# schematic.net
KiCad netlist of a schematic drawn in Altium Designer
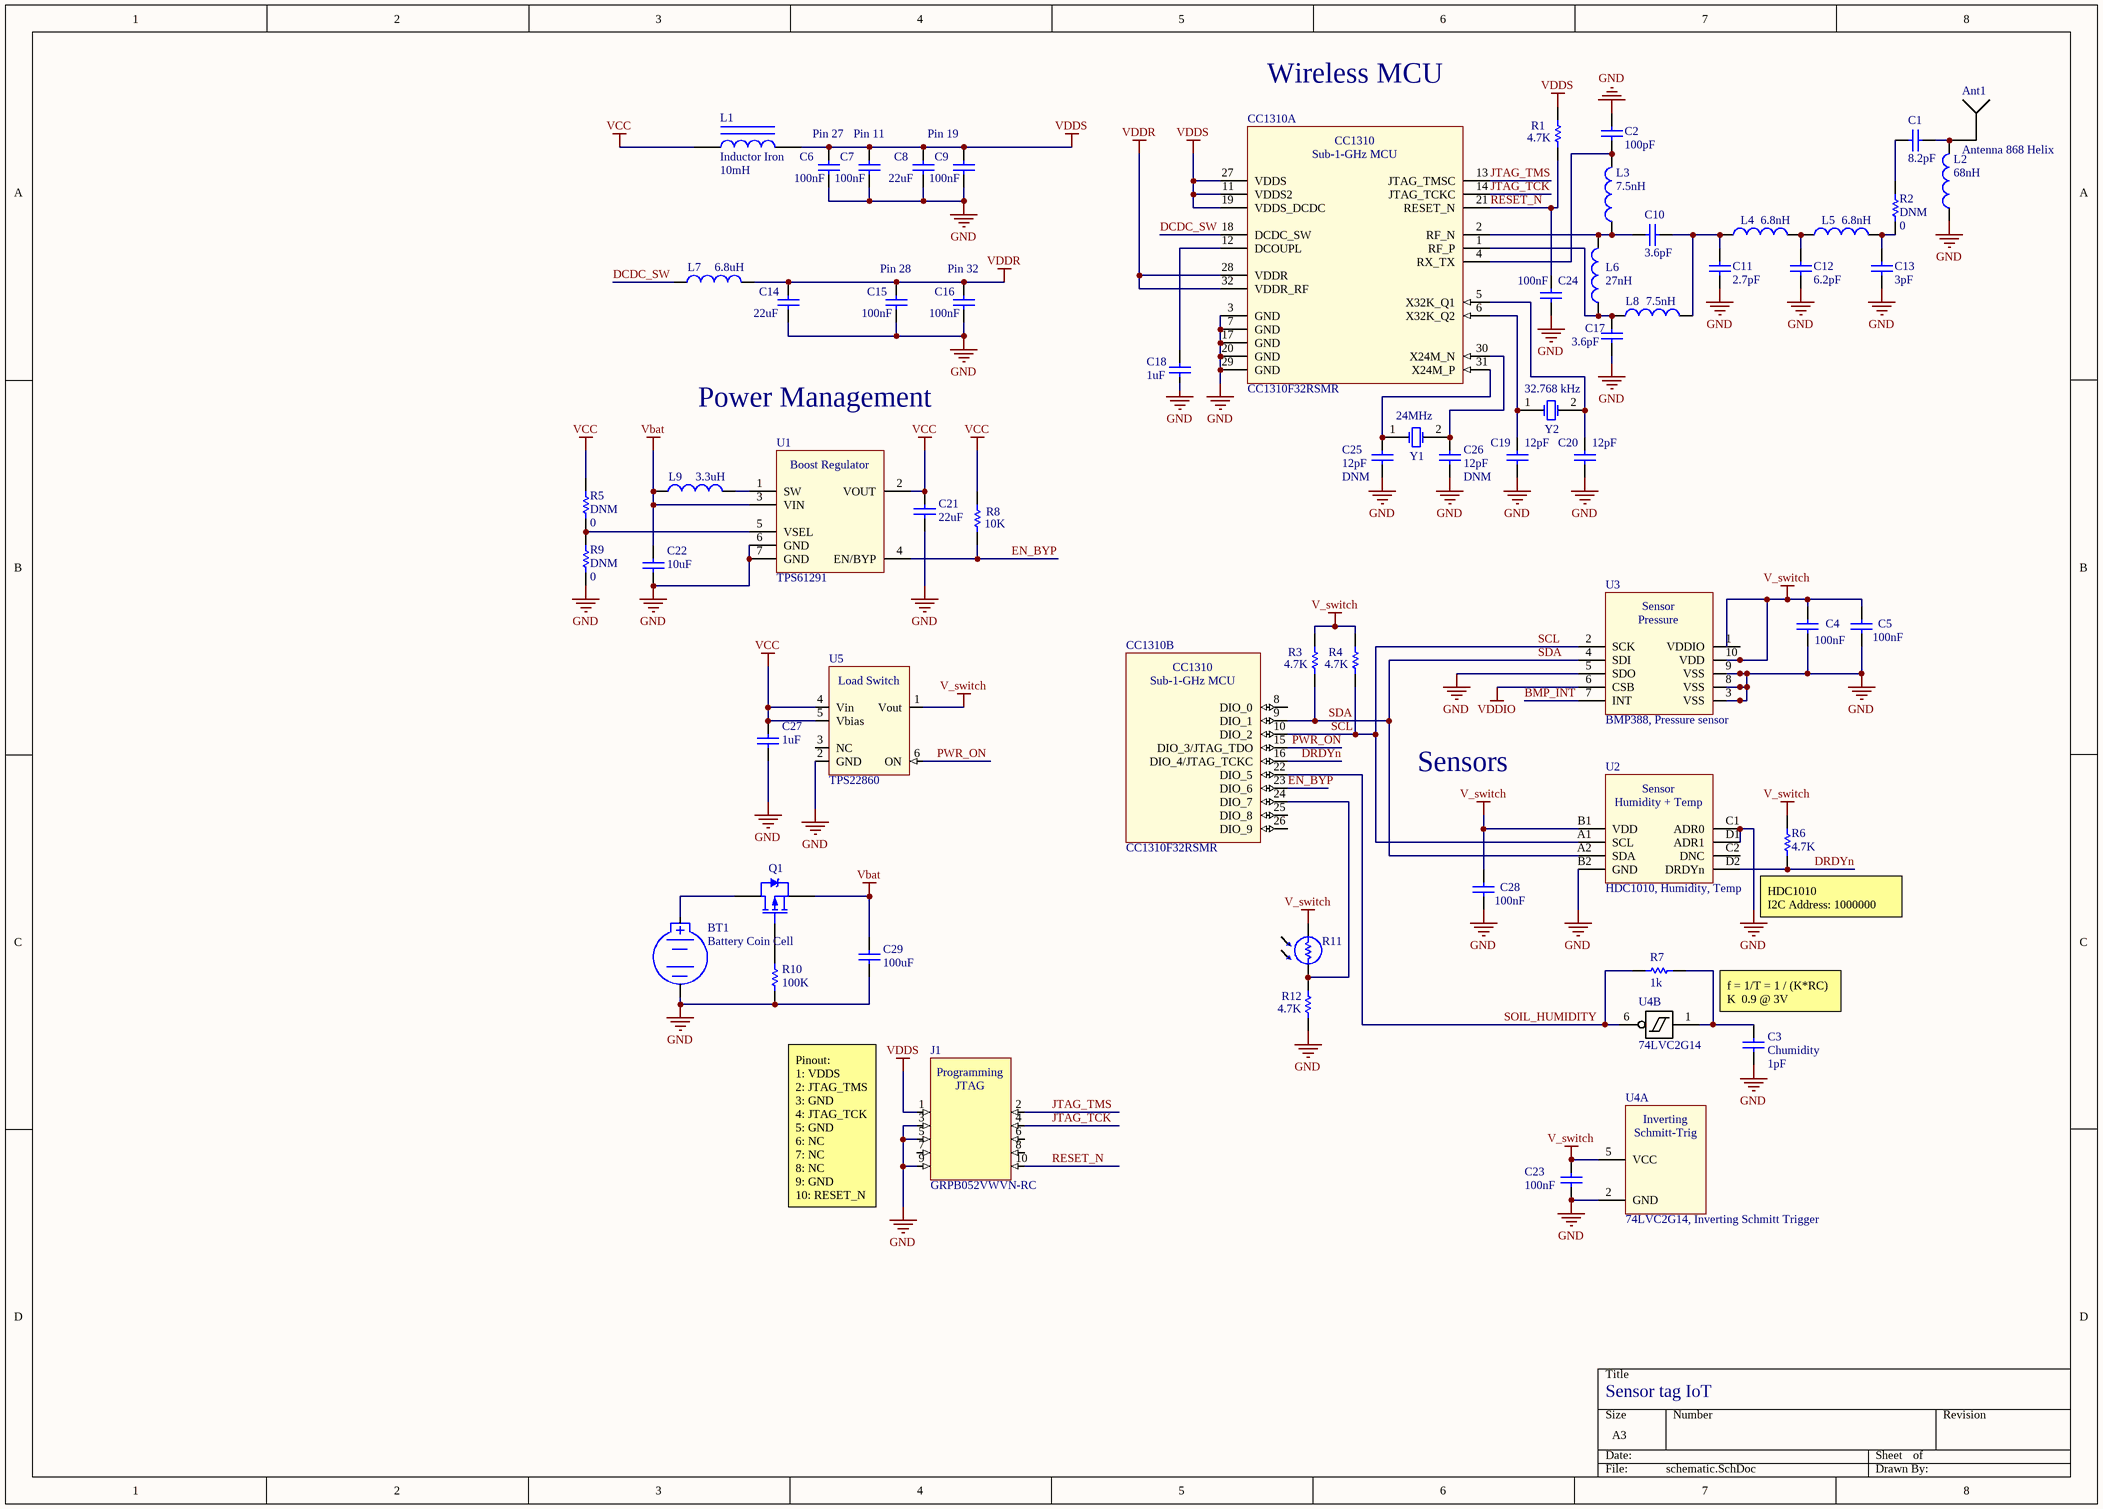
[diagram p0: schematic.SchDoc]

(export (version "E")
  (design (tool "Eeschema 10.0.6"))
  (components
    (comp (ref "Ant1")
      (value "Antenna 868 Helix")
      (footprint "Antenna_868_Helix")
      (libsource (lib "components") (part "Antenna 868 Helix"))
    )
    (comp (ref "BT1")
      (value "Battery Coin Cell")
      (footprint "SMTU2032-LF")
      (libsource (lib "components") (part "Battery Coin Cell"))
    )
    (comp (ref "C1")
      (value "8.2pF")
      (footprint "0402 (CAP)")
      (description "Capacitor")
      (fields (field (name "Comment") "Cap") (field (name "PUBLISHER") "Altium Limited"))
      (libsource (lib "Miscellaneous Devices") (part "Cap"))
    )
    (comp (ref "C2")
      (value "100pF")
      (footprint "0402 (CAP)")
      (description "Capacitor")
      (fields (field (name "Comment") "Cap") (field (name "PUBLISHER") "Altium Limited"))
      (libsource (lib "Miscellaneous Devices") (part "Cap"))
    )
    (comp (ref "C3")
      (value "Chumidity")
      (footprint "0402 (CAP)")
      (description "Capacitor")
      (fields (field (name "ALTIUM_VALUE") "1pF") (field (name "PUBLISHER") "Altium Limited"))
      (libsource (lib "Miscellaneous Devices") (part "Cap"))
    )
    (comp (ref "C4")
      (value "100nF")
      (footprint "0402 (CAP)")
      (description "Capacitor")
      (fields (field (name "Comment") "Cap") (field (name "PUBLISHER") "Altium Limited"))
      (libsource (lib "Miscellaneous Devices") (part "Cap"))
    )
    (comp (ref "C5")
      (value "100nF")
      (footprint "0402 (CAP)")
      (description "Capacitor")
      (fields (field (name "Comment") "Cap") (field (name "PUBLISHER") "Altium Limited"))
      (libsource (lib "Miscellaneous Devices") (part "Cap"))
    )
    (comp (ref "C6")
      (value "100nF")
      (footprint "0402 (CAP)")
      (description "Capacitor")
      (fields (field (name "Comment") "Cap") (field (name "PUBLISHER") "Altium Limited"))
      (libsource (lib "Miscellaneous Devices") (part "Cap"))
    )
    (comp (ref "C7")
      (value "100nF")
      (footprint "0402 (CAP)")
      (description "Capacitor")
      (fields (field (name "Comment") "Cap") (field (name "PUBLISHER") "Altium Limited"))
      (libsource (lib "Miscellaneous Devices") (part "Cap"))
    )
    (comp (ref "C8")
      (value "22uF")
      (footprint "0402 (CAP)")
      (description "Capacitor")
      (fields (field (name "Comment") "Cap") (field (name "PUBLISHER") "Altium Limited"))
      (libsource (lib "Miscellaneous Devices") (part "Cap"))
    )
    (comp (ref "C9")
      (value "100nF")
      (footprint "0402 (CAP)")
      (description "Capacitor")
      (fields (field (name "Comment") "Cap") (field (name "PUBLISHER") "Altium Limited"))
      (libsource (lib "Miscellaneous Devices") (part "Cap"))
    )
    (comp (ref "C10")
      (value "3.6pF")
      (footprint "0402 (CAP)")
      (description "Capacitor")
      (fields (field (name "Comment") "Cap") (field (name "PUBLISHER") "Altium Limited"))
      (libsource (lib "Miscellaneous Devices") (part "Cap"))
    )
    (comp (ref "C11")
      (value "2.7pF")
      (footprint "0402 (CAP)")
      (description "Capacitor")
      (fields (field (name "Comment") "Cap") (field (name "PUBLISHER") "Altium Limited"))
      (libsource (lib "Miscellaneous Devices") (part "Cap"))
    )
    (comp (ref "C12")
      (value "6.2pF")
      (footprint "0402 (CAP)")
      (description "Capacitor")
      (fields (field (name "Comment") "Cap") (field (name "PUBLISHER") "Altium Limited"))
      (libsource (lib "Miscellaneous Devices") (part "Cap"))
    )
    (comp (ref "C13")
      (value "3pF")
      (footprint "0402 (CAP)")
      (description "Capacitor")
      (fields (field (name "Comment") "Cap") (field (name "PUBLISHER") "Altium Limited"))
      (libsource (lib "Miscellaneous Devices") (part "Cap"))
    )
    (comp (ref "C14")
      (value "22uF")
      (footprint "0402 (CAP)")
      (description "Capacitor")
      (fields (field (name "Comment") "Cap") (field (name "PUBLISHER") "Altium Limited"))
      (libsource (lib "Miscellaneous Devices") (part "Cap"))
    )
    (comp (ref "C15")
      (value "100nF")
      (footprint "0402 (CAP)")
      (description "Capacitor")
      (fields (field (name "Comment") "Cap") (field (name "PUBLISHER") "Altium Limited"))
      (libsource (lib "Miscellaneous Devices") (part "Cap"))
    )
    (comp (ref "C16")
      (value "100nF")
      (footprint "0402 (CAP)")
      (description "Capacitor")
      (fields (field (name "Comment") "Cap") (field (name "PUBLISHER") "Altium Limited"))
      (libsource (lib "Miscellaneous Devices") (part "Cap"))
    )
    (comp (ref "C17")
      (value "3.6pF")
      (footprint "0402 (CAP)")
      (description "Capacitor")
      (fields (field (name "Comment") "Cap") (field (name "PUBLISHER") "Altium Limited"))
      (libsource (lib "Miscellaneous Devices") (part "Cap"))
    )
    (comp (ref "C18")
      (value "1uF")
      (footprint "0402 (CAP)")
      (description "Capacitor")
      (fields (field (name "Comment") "Cap") (field (name "PUBLISHER") "Altium Limited"))
      (libsource (lib "Miscellaneous Devices") (part "Cap"))
    )
    (comp (ref "C19")
      (value "12pF")
      (footprint "0402 (CAP)")
      (description "Capacitor")
      (fields (field (name "Comment") "Cap") (field (name "PUBLISHER") "Altium Limited"))
      (libsource (lib "Miscellaneous Devices") (part "Cap"))
    )
    (comp (ref "C20")
      (value "12pF")
      (footprint "0402 (CAP)")
      (description "Capacitor")
      (fields (field (name "Comment") "Cap") (field (name "PUBLISHER") "Altium Limited"))
      (libsource (lib "Miscellaneous Devices") (part "Cap"))
    )
    (comp (ref "C21")
      (value "22uF")
      (footprint "0402 (CAP)")
      (description "Capacitor")
      (fields (field (name "Comment") "Cap") (field (name "PUBLISHER") "Altium Limited"))
      (libsource (lib "Miscellaneous Devices") (part "Cap"))
    )
    (comp (ref "C22")
      (value "10uF")
      (footprint "0402 (CAP)")
      (description "Capacitor")
      (fields (field (name "Comment") "Cap") (field (name "PUBLISHER") "Altium Limited"))
      (libsource (lib "Miscellaneous Devices") (part "Cap"))
    )
    (comp (ref "C23")
      (value "100nF")
      (footprint "0402 (CAP)")
      (description "Capacitor")
      (fields (field (name "Comment") "Cap") (field (name "PUBLISHER") "Altium Limited"))
      (libsource (lib "Miscellaneous Devices") (part "Cap"))
    )
    (comp (ref "C24")
      (value "100nF")
      (footprint "0402 (CAP)")
      (description "Capacitor")
      (fields (field (name "Comment") "Cap") (field (name "PUBLISHER") "Altium Limited"))
      (libsource (lib "Miscellaneous Devices") (part "Cap"))
    )
    (comp (ref "C25")
      (value "DNM")
      (footprint "0402 (CAP)")
      (description "Capacitor")
      (fields (field (name "ALTIUM_VALUE") "12pF") (field (name "PUBLISHER") "Altium Limited"))
      (libsource (lib "Miscellaneous Devices") (part "Cap"))
    )
    (comp (ref "C26")
      (value "DNM")
      (footprint "0402 (CAP)")
      (description "Capacitor")
      (fields (field (name "ALTIUM_VALUE") "12pF") (field (name "PUBLISHER") "Altium Limited"))
      (libsource (lib "Miscellaneous Devices") (part "Cap"))
    )
    (comp (ref "C27")
      (value "1uF")
      (footprint "0402 (CAP)")
      (description "Capacitor")
      (fields (field (name "Comment") "Cap") (field (name "PUBLISHER") "Altium Limited"))
      (libsource (lib "Miscellaneous Devices") (part "Cap"))
    )
    (comp (ref "C28")
      (value "100nF")
      (footprint "0402 (CAP)")
      (description "Capacitor")
      (fields (field (name "Comment") "Cap") (field (name "PUBLISHER") "Altium Limited"))
      (libsource (lib "Miscellaneous Devices") (part "Cap"))
    )
    (comp (ref "C29")
      (value "100uF")
      (footprint "0402 (CAP)")
      (description "Capacitor")
      (fields (field (name "Comment") "Cap") (field (name "PUBLISHER") "Altium Limited"))
      (libsource (lib "Miscellaneous Devices") (part "Cap"))
    )
    (comp (ref "CC1310")
      (value "CC1310F32RSMR")
      (footprint "CC1310F32RSMR")
      (libsource (lib "components") (part "CC1310F32RSMR"))
    )
    (comp (ref "J1") (value "GRPB052VWVN-RC") (libsource (lib "connectors") (part "GRPB052VWVN-RC")))
    (comp (ref "L1")
      (value "Inductor Iron")
      (footprint "0603 (IND)")
      (description "Magnetic-Core Inductor")
      (fields (field (name "ALTIUM_VALUE") "10mH") (field (name "PUBLISHER") "Altium Limited"))
      (libsource (lib "Miscellaneous Devices") (part "Inductor Iron"))
    )
    (comp (ref "L2")
      (value "68nH")
      (footprint "0603 (IND)")
      (description "Inductor")
      (fields (field (name "PUBLISHER") "Altium Limited"))
      (libsource (lib "Miscellaneous Devices") (part "Inductor"))
    )
    (comp (ref "L3")
      (value "7.5nH")
      (footprint "0603 (IND)")
      (description "Inductor")
      (fields (field (name "PUBLISHER") "Altium Limited"))
      (libsource (lib "") (part "Inductor_1"))
    )
    (comp (ref "L4")
      (value "6.8nH")
      (footprint "0603 (IND)")
      (description "Inductor")
      (fields (field (name "PUBLISHER") "Altium Limited"))
      (libsource (lib "Miscellaneous Devices") (part "Inductor"))
    )
    (comp (ref "L5")
      (value "6.8nH")
      (footprint "0603 (IND)")
      (description "Inductor")
      (fields (field (name "PUBLISHER") "Altium Limited"))
      (libsource (lib "Miscellaneous Devices") (part "Inductor"))
    )
    (comp (ref "L6")
      (value "27nH")
      (footprint "0603 (IND)")
      (description "Inductor")
      (fields (field (name "PUBLISHER") "Altium Limited"))
      (libsource (lib "Miscellaneous Devices") (part "Inductor"))
    )
    (comp (ref "L7")
      (value "6.8uH")
      (footprint "0603 (IND)")
      (description "Inductor")
      (fields (field (name "PUBLISHER") "Altium Limited"))
      (libsource (lib "") (part "Inductor_1"))
    )
    (comp (ref "L8")
      (value "7.5nH")
      (footprint "0603 (IND)")
      (description "Inductor")
      (fields (field (name "PUBLISHER") "Altium Limited"))
      (libsource (lib "Miscellaneous Devices") (part "Inductor"))
    )
    (comp (ref "L9")
      (value "3.3uH")
      (footprint "0603 (IND)")
      (description "Inductor")
      (fields (field (name "PUBLISHER") "Altium Limited"))
      (libsource (lib "") (part "Inductor_1"))
    )
    (comp (ref "Q1")
      (value "PMOS-2")
      (footprint "TO-220AB")
      (description "P-Channel Power MOSFET")
      (fields (field (name "PUBLISHER") "Altium Limited"))
      (libsource (lib "Miscellaneous Devices") (part "PMOS-2"))
    )
    (comp (ref "R1")
      (value "4.7K")
      (footprint "0402 (RES)")
      (description "Resistor")
      (fields (field (name "Comment") "Res1") (field (name "PUBLISHER") "Altium Limited"))
      (libsource (lib "Miscellaneous Devices") (part "Res1"))
    )
    (comp (ref "R2")
      (value "DNM")
      (footprint "0402 (RES)")
      (description "Resistor")
      (fields (field (name "ALTIUM_VALUE") "0") (field (name "PUBLISHER") "Altium Limited"))
      (libsource (lib "Miscellaneous Devices") (part "Res1"))
    )
    (comp (ref "R3")
      (value "4.7K")
      (footprint "0402 (RES)")
      (description "Resistor")
      (fields (field (name "Comment") "Res1") (field (name "PUBLISHER") "Altium Limited"))
      (libsource (lib "Miscellaneous Devices") (part "Res1"))
    )
    (comp (ref "R4")
      (value "4.7K")
      (footprint "0402 (RES)")
      (description "Resistor")
      (fields (field (name "Comment") "Res1") (field (name "PUBLISHER") "Altium Limited"))
      (libsource (lib "Miscellaneous Devices") (part "Res1"))
    )
    (comp (ref "R5")
      (value "DNM")
      (footprint "0402 (RES)")
      (description "Resistor")
      (fields (field (name "ALTIUM_VALUE") "0") (field (name "PUBLISHER") "Altium Limited"))
      (libsource (lib "Miscellaneous Devices") (part "Res1"))
    )
    (comp (ref "R6")
      (value "4.7K")
      (footprint "0402 (RES)")
      (description "Resistor")
      (fields (field (name "Comment") "Res1") (field (name "PUBLISHER") "Altium Limited"))
      (libsource (lib "Miscellaneous Devices") (part "Res1"))
    )
    (comp (ref "R7")
      (value "1k")
      (footprint "0402 (RES)")
      (description "Resistor")
      (fields (field (name "Comment") "Rcharge") (field (name "PUBLISHER") "Altium Limited"))
      (libsource (lib "Miscellaneous Devices") (part "Res1"))
    )
    (comp (ref "R8")
      (value "10K")
      (footprint "0402 (RES)")
      (description "Resistor")
      (fields (field (name "Comment") "Res1") (field (name "PUBLISHER") "Altium Limited"))
      (libsource (lib "Miscellaneous Devices") (part "Res1"))
    )
    (comp (ref "R9")
      (value "DNM")
      (footprint "0402 (RES)")
      (description "Resistor")
      (fields (field (name "ALTIUM_VALUE") "0") (field (name "PUBLISHER") "Altium Limited"))
      (libsource (lib "Miscellaneous Devices") (part "Res1"))
    )
    (comp (ref "R10")
      (value "100K")
      (footprint "0402 (RES)")
      (description "Resistor")
      (fields (field (name "Comment") "Res1") (field (name "PUBLISHER") "Altium Limited"))
      (libsource (lib "Miscellaneous Devices") (part "Res1"))
    )
    (comp (ref "R11") (value "Photo Resistor") (libsource (lib "components") (part "Photo Resistor")))
    (comp (ref "R12")
      (value "4.7K")
      (footprint "0402 (RES)")
      (description "Resistor")
      (fields (field (name "Comment") "Res1") (field (name "PUBLISHER") "Altium Limited"))
      (libsource (lib "Miscellaneous Devices") (part "Res1"))
    )
    (comp (ref "U1")
      (value "TPS61291")
      (footprint "TPS61291")
      (libsource (lib "components") (part "TPS61291"))
    )
    (comp (ref "U2")
      (value "HDC1010, Humidity, Temp")
      (footprint "HDC1010")
      (libsource (lib "components") (part "HDC1010"))
    )
    (comp (ref "U3")
      (value "BMP388, Pressure sensor")
      (footprint "BMP388")
      (libsource (lib "components") (part "BMP388"))
    )
    (comp (ref "U4")
      (value "74LVC2G14, Inverting Schmitt Trigger")
      (footprint "74LVC2G14")
      (libsource (lib "components") (part "74LVC2G14"))
    )
    (comp (ref "U5")
      (value "TPS22860")
      (footprint "SOT23-5")
      (libsource (lib "components") (part "TPS22860"))
    )
    (comp (ref "Y1")
      (value "24MHz")
      (footprint "R38")
      (description "Crystal Oscillator")
      (fields (field (name "PUBLISHER") "Altium Limited"))
      (libsource (lib "Miscellaneous Devices") (part "XTAL"))
    )
    (comp (ref "Y2")
      (value "32.768 kHz")
      (footprint "R38")
      (description "Crystal Oscillator")
      (fields (field (name "PUBLISHER") "Altium Limited"))
      (libsource (lib "Miscellaneous Devices") (part "XTAL"))
    )
  )
  (nets
    (net (code "1") (name "/BMP_INT") (class "Default")
      (node (ref "U3") (pin "7") (pinfunction "INT_7") (pintype "passive"))
    )
    (net (code "2") (name "/DCDC_SW") (class "Default")
      (node (ref "CC1310") (pin "18") (pinfunction "DCDC_SW_18") (pintype "power_in"))
      (node (ref "L7") (pin "1") (pinfunction "1_1") (pintype "passive"))
    )
    (net (code "3") (name "/DRDYn") (class "Default")
      (node (ref "CC1310") (pin "16") (pinfunction "DIO_4/JTAG_TCKC_16") (pintype "bidirectional"))
      (node (ref "R6") (pin "2") (pinfunction "2_2") (pintype "passive"))
      (node (ref "U2") (pin "D2") (pinfunction "DRDYn_D2") (pintype "passive"))
    )
    (net (code "4") (name "/EN_BYP") (class "Default")
      (node (ref "CC1310") (pin "23") (pinfunction "DIO_6_23") (pintype "bidirectional"))
      (node (ref "R8") (pin "2") (pinfunction "2_2") (pintype "passive"))
      (node (ref "U1") (pin "4") (pinfunction "EN/BYP_4") (pintype "passive"))
    )
    (net (code "5") (name "/JTAG_TCK") (class "Default")
      (node (ref "CC1310") (pin "14") (pinfunction "JTAG_TCKC_14") (pintype "passive"))
      (node (ref "J1") (pin "4") (pinfunction "JTAG_TCK_4") (pintype "input"))
    )
    (net (code "6") (name "/JTAG_TMS") (class "Default")
      (node (ref "CC1310") (pin "13") (pinfunction "JTAG_TMSC_13") (pintype "passive"))
      (node (ref "J1") (pin "2") (pinfunction "JTAG_TMS_2") (pintype "input"))
    )
    (net (code "7") (name "/PWR_ON") (class "Default")
      (node (ref "CC1310") (pin "15") (pinfunction "DIO_3/JTAG_TDO_15") (pintype "bidirectional"))
      (node (ref "U5") (pin "6") (pinfunction "ON_6") (pintype "input"))
    )
    (net (code "8") (name "/RESET_N") (class "Default")
      (node (ref "C24") (pin "1") (pinfunction "1_1") (pintype "passive"))
      (node (ref "CC1310") (pin "21") (pinfunction "RESET_N_21") (pintype "passive"))
      (node (ref "J1") (pin "10") (pinfunction "RESET_N_10") (pintype "input"))
      (node (ref "R1") (pin "1") (pinfunction "1_1") (pintype "passive"))
    )
    (net (code "9") (name "/SCL") (class "Default")
      (node (ref "CC1310") (pin "10") (pinfunction "DIO_2_10") (pintype "bidirectional"))
      (node (ref "R4") (pin "1") (pinfunction "1_1") (pintype "passive"))
      (node (ref "U2") (pin "A1") (pinfunction "SCL_A1") (pintype "passive"))
      (node (ref "U3") (pin "2") (pinfunction "SCK_2") (pintype "passive"))
    )
    (net (code "10") (name "/SDA") (class "Default")
      (node (ref "CC1310") (pin "9") (pinfunction "DIO_1_9") (pintype "bidirectional"))
      (node (ref "R3") (pin "1") (pinfunction "1_1") (pintype "passive"))
      (node (ref "U2") (pin "A2") (pinfunction "SDA_A2") (pintype "passive"))
      (node (ref "U3") (pin "4") (pinfunction "SDI_4") (pintype "passive"))
    )
    (net (code "11") (name "/SOIL_HUMIDITY") (class "Default")
      (node (ref "CC1310") (pin "22") (pinfunction "DIO_5_22") (pintype "bidirectional"))
      (node (ref "R7") (pin "2") (pinfunction "2_2") (pintype "passive"))
      (node (ref "U4") (pin "6") (pinfunction "1Y_6") (pintype "passive"))
    )
    (net (code "12") (name "GND") (class "Default")
      (node (ref "BT1") (pin "2") (pinfunction "Negative_2") (pintype "passive"))
      (node (ref "C11") (pin "2") (pinfunction "2_2") (pintype "passive"))
      (node (ref "C12") (pin "2") (pinfunction "2_2") (pintype "passive"))
      (node (ref "C13") (pin "2") (pinfunction "2_2") (pintype "passive"))
      (node (ref "C14") (pin "1") (pinfunction "1_1") (pintype "passive"))
      (node (ref "C15") (pin "1") (pinfunction "1_1") (pintype "passive"))
      (node (ref "C16") (pin "1") (pinfunction "1_1") (pintype "passive"))
      (node (ref "C17") (pin "2") (pinfunction "2_2") (pintype "passive"))
      (node (ref "C18") (pin "1") (pinfunction "1_1") (pintype "passive"))
      (node (ref "C19") (pin "1") (pinfunction "1_1") (pintype "passive"))
      (node (ref "C2") (pin "1") (pinfunction "1_1") (pintype "passive"))
      (node (ref "C20") (pin "1") (pinfunction "1_1") (pintype "passive"))
      (node (ref "C21") (pin "1") (pinfunction "1_1") (pintype "passive"))
      (node (ref "C22") (pin "1") (pinfunction "1_1") (pintype "passive"))
      (node (ref "C23") (pin "1") (pinfunction "1_1") (pintype "passive"))
      (node (ref "C24") (pin "2") (pinfunction "2_2") (pintype "passive"))
      (node (ref "C25") (pin "1") (pinfunction "1_1") (pintype "passive"))
      (node (ref "C26") (pin "1") (pinfunction "1_1") (pintype "passive"))
      (node (ref "C27") (pin "1") (pinfunction "1_1") (pintype "passive"))
      (node (ref "C28") (pin "1") (pinfunction "1_1") (pintype "passive"))
      (node (ref "C29") (pin "1") (pinfunction "1_1") (pintype "passive"))
      (node (ref "C3") (pin "1") (pinfunction "1_1") (pintype "passive"))
      (node (ref "C4") (pin "1") (pinfunction "1_1") (pintype "passive"))
      (node (ref "C5") (pin "1") (pinfunction "1_1") (pintype "passive"))
      (node (ref "C6") (pin "1") (pinfunction "1_1") (pintype "passive"))
      (node (ref "C7") (pin "1") (pinfunction "1_1") (pintype "passive"))
      (node (ref "C8") (pin "1") (pinfunction "1_1") (pintype "passive"))
      (node (ref "C9") (pin "1") (pinfunction "1_1") (pintype "passive"))
      (node (ref "CC1310") (pin "17") (pinfunction "GND_17") (pintype "passive"))
      (node (ref "CC1310") (pin "20") (pinfunction "GND_20") (pintype "passive"))
      (node (ref "CC1310") (pin "29") (pinfunction "GND_29") (pintype "passive"))
      (node (ref "CC1310") (pin "3") (pinfunction "GND_3") (pintype "passive"))
      (node (ref "CC1310") (pin "7") (pinfunction "GND_7") (pintype "passive"))
      (node (ref "J1") (pin "3") (pinfunction "GND_3") (pintype "input"))
      (node (ref "J1") (pin "5") (pinfunction "GND_5") (pintype "input"))
      (node (ref "J1") (pin "9") (pinfunction "GND_9") (pintype "input"))
      (node (ref "L2") (pin "2") (pinfunction "2_2") (pintype "passive"))
      (node (ref "R10") (pin "2") (pinfunction "2_2") (pintype "passive"))
      (node (ref "R12") (pin "1") (pinfunction "1_1") (pintype "passive"))
      (node (ref "R9") (pin "2") (pinfunction "2_2") (pintype "passive"))
      (node (ref "U1") (pin "6") (pinfunction "GND_6") (pintype "passive"))
      (node (ref "U1") (pin "7") (pinfunction "GND_7") (pintype "passive"))
      (node (ref "U2") (pin "B2") (pinfunction "GND_B2") (pintype "passive"))
      (node (ref "U2") (pin "C1") (pinfunction "ADR0_C1") (pintype "passive"))
      (node (ref "U2") (pin "D1") (pinfunction "ADR1_D1") (pintype "passive"))
      (node (ref "U3") (pin "3") (pinfunction "VSS_3") (pintype "passive"))
      (node (ref "U3") (pin "5") (pinfunction "SDO_5") (pintype "passive"))
      (node (ref "U3") (pin "8") (pinfunction "VSS_8") (pintype "passive"))
      (node (ref "U3") (pin "9") (pinfunction "VSS_9") (pintype "passive"))
      (node (ref "U4") (pin "2") (pinfunction "GND_2") (pintype "passive"))
      (node (ref "U5") (pin "2") (pinfunction "GND_2") (pintype "power_in"))
    )
    (net (code "13") (name "Net-(Ant1-Pad0)") (class "Default")
      (node (ref "Ant1") (pin "0") (pinfunction "0_0") (pintype "passive"))
      (node (ref "C1") (pin "2") (pinfunction "2_2") (pintype "passive"))
      (node (ref "L2") (pin "1") (pinfunction "1_1") (pintype "passive"))
    )
    (net (code "14") (name "Net-(BT1-Positive)") (class "Default")
      (node (ref "BT1") (pin "1") (pinfunction "Positive_1") (pintype "passive"))
      (node (ref "Q1") (pin "2") (pinfunction "D_2") (pintype "passive"))
    )
    (net (code "15") (name "Net-(C1-Pad1)") (class "Default")
      (node (ref "C1") (pin "1") (pinfunction "1_1") (pintype "passive"))
      (node (ref "R2") (pin "1") (pinfunction "1_1") (pintype "passive"))
    )
    (net (code "16") (name "Net-(C10-Pad2)") (class "Default")
      (node (ref "C10") (pin "2") (pinfunction "2_2") (pintype "passive"))
      (node (ref "C11") (pin "1") (pinfunction "1_1") (pintype "passive"))
      (node (ref "L4") (pin "2") (pinfunction "2_2") (pintype "passive"))
      (node (ref "L8") (pin "1") (pinfunction "1_1") (pintype "passive"))
    )
    (net (code "17") (name "Net-(C12-Pad1)") (class "Default")
      (node (ref "C12") (pin "1") (pinfunction "1_1") (pintype "passive"))
      (node (ref "L4") (pin "1") (pinfunction "1_1") (pintype "passive"))
      (node (ref "L5") (pin "2") (pinfunction "2_2") (pintype "passive"))
    )
    (net (code "18") (name "Net-(C13-Pad1)") (class "Default")
      (node (ref "C13") (pin "1") (pinfunction "1_1") (pintype "passive"))
      (node (ref "L5") (pin "1") (pinfunction "1_1") (pintype "passive"))
      (node (ref "R2") (pin "2") (pinfunction "2_2") (pintype "passive"))
    )
    (net (code "19") (name "Net-(CC1310A-DCOUPL)") (class "Default")
      (node (ref "C18") (pin "2") (pinfunction "2_2") (pintype "passive"))
      (node (ref "CC1310") (pin "12") (pinfunction "DCOUPL_12") (pintype "power_in"))
    )
    (net (code "20") (name "Net-(CC1310A-RF_N)") (class "Default")
      (node (ref "C10") (pin "1") (pinfunction "1_1") (pintype "passive"))
      (node (ref "CC1310") (pin "2") (pinfunction "RF_N_2") (pintype "passive"))
      (node (ref "L3") (pin "1") (pinfunction "1_1") (pintype "passive"))
      (node (ref "L6") (pin "1") (pinfunction "1_1") (pintype "passive"))
    )
    (net (code "21") (name "Net-(CC1310A-RF_P)") (class "Default")
      (node (ref "C17") (pin "1") (pinfunction "1_1") (pintype "passive"))
      (node (ref "CC1310") (pin "1") (pinfunction "RF_P_1") (pintype "passive"))
      (node (ref "L6") (pin "2") (pinfunction "2_2") (pintype "passive"))
      (node (ref "L8") (pin "2") (pinfunction "2_2") (pintype "passive"))
    )
    (net (code "22") (name "Net-(CC1310A-RX_TX)") (class "Default")
      (node (ref "C2") (pin "2") (pinfunction "2_2") (pintype "passive"))
      (node (ref "CC1310") (pin "4") (pinfunction "RX_TX_4") (pintype "passive"))
      (node (ref "L3") (pin "2") (pinfunction "2_2") (pintype "passive"))
    )
    (net (code "23") (name "Net-(CC1310A-X24M_N)") (class "Default")
      (node (ref "C26") (pin "2") (pinfunction "2_2") (pintype "passive"))
      (node (ref "CC1310") (pin "30") (pinfunction "X24M_N_30") (pintype "input"))
      (node (ref "Y1") (pin "2") (pinfunction "OSC2_2") (pintype "passive"))
    )
    (net (code "24") (name "Net-(CC1310A-X24M_P)") (class "Default")
      (node (ref "C25") (pin "2") (pinfunction "2_2") (pintype "passive"))
      (node (ref "CC1310") (pin "31") (pinfunction "X24M_P_31") (pintype "input"))
      (node (ref "Y1") (pin "1") (pinfunction "OSC1_1") (pintype "passive"))
    )
    (net (code "25") (name "Net-(CC1310A-X32K_Q1)") (class "Default")
      (node (ref "C20") (pin "2") (pinfunction "2_2") (pintype "passive"))
      (node (ref "CC1310") (pin "5") (pinfunction "X32K_Q1_5") (pintype "input"))
      (node (ref "Y2") (pin "2") (pinfunction "OSC2_2") (pintype "passive"))
    )
    (net (code "26") (name "Net-(CC1310A-X32K_Q2)") (class "Default")
      (node (ref "C19") (pin "2") (pinfunction "2_2") (pintype "passive"))
      (node (ref "CC1310") (pin "6") (pinfunction "X32K_Q2_6") (pintype "input"))
      (node (ref "Y2") (pin "1") (pinfunction "OSC1_1") (pintype "passive"))
    )
    (net (code "27") (name "Net-(CC1310B-DIO_7)") (class "Default")
      (node (ref "CC1310") (pin "24") (pinfunction "DIO_7_24") (pintype "bidirectional"))
      (node (ref "R11") (pin "2") (pinfunction "2_2") (pintype "passive"))
      (node (ref "R12") (pin "2") (pinfunction "2_2") (pintype "passive"))
    )
    (net (code "28") (name "Net-(Q1-G)") (class "Default")
      (node (ref "Q1") (pin "1") (pinfunction "G_1") (pintype "passive"))
      (node (ref "R10") (pin "1") (pinfunction "1_1") (pintype "passive"))
    )
    (net (code "29") (name "Net-(U1-SW)") (class "Default")
      (node (ref "L9") (pin "2") (pinfunction "2_2") (pintype "passive"))
      (node (ref "U1") (pin "1") (pinfunction "SW_1") (pintype "passive"))
    )
    (net (code "30") (name "Net-(U1-VSEL)") (class "Default")
      (node (ref "R5") (pin "2") (pinfunction "2_2") (pintype "passive"))
      (node (ref "R9") (pin "1") (pinfunction "1_1") (pintype "passive"))
      (node (ref "U1") (pin "5") (pinfunction "VSEL_5") (pintype "passive"))
    )
    (net (code "31") (name "Net-(U4B-1A)") (class "Default")
      (node (ref "C3") (pin "2") (pinfunction "2_2") (pintype "passive"))
      (node (ref "R7") (pin "1") (pinfunction "1_1") (pintype "passive"))
      (node (ref "U4") (pin "1") (pinfunction "1A_1") (pintype "passive"))
    )
    (net (code "32") (name "VCC") (class "Default")
      (node (ref "C21") (pin "2") (pinfunction "2_2") (pintype "passive"))
      (node (ref "C27") (pin "2") (pinfunction "2_2") (pintype "passive"))
      (node (ref "L1") (pin "1") (pinfunction "1_1") (pintype "passive"))
      (node (ref "R5") (pin "1") (pinfunction "1_1") (pintype "passive"))
      (node (ref "R8") (pin "1") (pinfunction "1_1") (pintype "passive"))
      (node (ref "U1") (pin "2") (pinfunction "VOUT_2") (pintype "passive"))
      (node (ref "U5") (pin "4") (pinfunction "Vin_4") (pintype "power_in"))
      (node (ref "U5") (pin "5") (pinfunction "Vbias_5") (pintype "power_in"))
    )
    (net (code "33") (name "VDDIO") (class "Default")
      (node (ref "U3") (pin "6") (pinfunction "CSB_6") (pintype "passive"))
    )
    (net (code "34") (name "VDDR") (class "Default")
      (node (ref "C14") (pin "2") (pinfunction "2_2") (pintype "passive"))
      (node (ref "C15") (pin "2") (pinfunction "2_2") (pintype "passive"))
      (node (ref "C16") (pin "2") (pinfunction "2_2") (pintype "passive"))
      (node (ref "CC1310") (pin "28") (pinfunction "VDDR_28") (pintype "power_in"))
      (node (ref "CC1310") (pin "32") (pinfunction "VDDR_RF_32") (pintype "power_in"))
      (node (ref "L7") (pin "2") (pinfunction "2_2") (pintype "passive"))
    )
    (net (code "35") (name "VDDS") (class "Default")
      (node (ref "C6") (pin "2") (pinfunction "2_2") (pintype "passive"))
      (node (ref "C7") (pin "2") (pinfunction "2_2") (pintype "passive"))
      (node (ref "C8") (pin "2") (pinfunction "2_2") (pintype "passive"))
      (node (ref "C9") (pin "2") (pinfunction "2_2") (pintype "passive"))
      (node (ref "CC1310") (pin "11") (pinfunction "VDDS2_11") (pintype "passive"))
      (node (ref "CC1310") (pin "19") (pinfunction "VDDS_DCDC_19") (pintype "passive"))
      (node (ref "CC1310") (pin "27") (pinfunction "VDDS_27") (pintype "passive"))
      (node (ref "J1") (pin "1") (pinfunction "VDDS_1") (pintype "input"))
      (node (ref "L1") (pin "2") (pinfunction "2_2") (pintype "passive"))
      (node (ref "R1") (pin "2") (pinfunction "2_2") (pintype "passive"))
    )
    (net (code "36") (name "V_switch") (class "Default")
      (node (ref "C23") (pin "2") (pinfunction "2_2") (pintype "passive"))
      (node (ref "C28") (pin "2") (pinfunction "2_2") (pintype "passive"))
      (node (ref "C4") (pin "2") (pinfunction "2_2") (pintype "passive"))
      (node (ref "C5") (pin "2") (pinfunction "2_2") (pintype "passive"))
      (node (ref "R11") (pin "1") (pinfunction "1_1") (pintype "passive"))
      (node (ref "R3") (pin "2") (pinfunction "2_2") (pintype "passive"))
      (node (ref "R4") (pin "2") (pinfunction "2_2") (pintype "passive"))
      (node (ref "R6") (pin "1") (pinfunction "1_1") (pintype "passive"))
      (node (ref "U2") (pin "B1") (pinfunction "VDD_B1") (pintype "passive"))
      (node (ref "U3") (pin "10") (pinfunction "VDD_10") (pintype "passive"))
      (node (ref "U4") (pin "5") (pinfunction "VCC_5") (pintype "passive"))
      (node (ref "U5") (pin "1") (pinfunction "Vout_1") (pintype "power_in"))
    )
    (net (code "37") (name "Vbat") (class "Default")
      (node (ref "C22") (pin "2") (pinfunction "2_2") (pintype "passive"))
      (node (ref "C29") (pin "2") (pinfunction "2_2") (pintype "passive"))
      (node (ref "L9") (pin "1") (pinfunction "1_1") (pintype "passive"))
      (node (ref "Q1") (pin "3") (pinfunction "S_3") (pintype "passive"))
      (node (ref "U1") (pin "3") (pinfunction "VIN_3") (pintype "passive"))
    )
    (net (code "38") (name "unconnected-(CC1310B-DIO_0-Pad8)") (class "Default")
      (node (ref "CC1310") (pin "8") (pinfunction "DIO_0_8") (pintype "bidirectional"))
    )
    (net (code "39") (name "unconnected-(CC1310B-DIO_8-Pad25)") (class "Default")
      (node (ref "CC1310") (pin "25") (pinfunction "DIO_8_25") (pintype "bidirectional"))
    )
    (net (code "40") (name "unconnected-(CC1310B-DIO_9-Pad26)") (class "Default")
      (node (ref "CC1310") (pin "26") (pinfunction "DIO_9_26") (pintype "bidirectional"))
    )
    (net (code "41") (name "unconnected-(J1-NC-Pad6)") (class "Default")
      (node (ref "J1") (pin "6") (pinfunction "NC_6") (pintype "input"))
    )
    (net (code "42") (name "unconnected-(J1-NC-Pad7)") (class "Default")
      (node (ref "J1") (pin "7") (pinfunction "NC_7") (pintype "input"))
    )
    (net (code "43") (name "unconnected-(J1-NC-Pad8)") (class "Default")
      (node (ref "J1") (pin "8") (pinfunction "NC_8") (pintype "input"))
    )
    (net (code "44") (name "unconnected-(U2-DNC-PadC2)") (class "Default")
      (node (ref "U2") (pin "C2") (pinfunction "DNC_C2") (pintype "passive"))
    )
    (net (code "45") (name "unconnected-(U3-VDDIO-Pad1)") (class "Default")
      (node (ref "U3") (pin "1") (pinfunction "VDDIO_1") (pintype "passive"))
    )
    (net (code "46") (name "unconnected-(U5-NC-Pad3)") (class "Default")
      (node (ref "U5") (pin "3") (pinfunction "NC_3") (pintype "passive"))
    )
  )
)
